# pixEmilyPdb.net
KiCad netlist of a schematic drawn in EAGLE
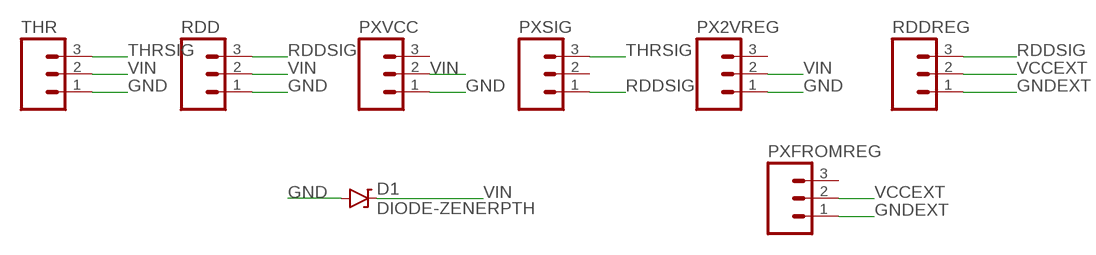
[diagram p0: schematic, sheet 1]

(export (version "E")
  (design (tool "Eeschema 10.0.6"))
  (components
    (comp (ref "D1")
      (value "DIODE-ZENERPTH")
      (footprint "eagle-import:DIODE-ZENER")
      (libsource (lib "eagle-import") (part "DIODE-ZENERPTH"))
    )
    (comp (ref "PX2VREG")
      (value "M03PTH")
      (footprint "eagle-import:1X03")
      (libsource (lib "eagle-import") (part "M03PTH"))
    )
    (comp (ref "PXFROMREG")
      (value "M03PTH")
      (footprint "eagle-import:1X03")
      (libsource (lib "eagle-import") (part "M03PTH"))
    )
    (comp (ref "PXSIG")
      (value "M03PTH")
      (footprint "eagle-import:1X03")
      (libsource (lib "eagle-import") (part "M03PTH"))
    )
    (comp (ref "PXVCC")
      (value "M03PTH")
      (footprint "eagle-import:1X03")
      (libsource (lib "eagle-import") (part "M03PTH"))
    )
    (comp (ref "RDD")
      (value "M03PTH")
      (footprint "eagle-import:1X03")
      (libsource (lib "eagle-import") (part "M03PTH"))
    )
    (comp (ref "RDDREG")
      (value "M03PTH")
      (footprint "eagle-import:1X03")
      (libsource (lib "eagle-import") (part "M03PTH"))
    )
    (comp (ref "THR")
      (value "M03PTH")
      (footprint "eagle-import:1X03")
      (libsource (lib "eagle-import") (part "M03PTH"))
    )
  )
  (nets
    (net (code "1") (name "/GND") (class "Default")
      (node (ref "D1") (pin "P$2") (pinfunction "A_P$2") (pintype "passive"))
      (node (ref "PX2VREG") (pin "1") (pinfunction "1_1") (pintype "passive"))
      (node (ref "PXVCC") (pin "1") (pinfunction "1_1") (pintype "passive"))
      (node (ref "RDD") (pin "1") (pinfunction "1_1") (pintype "passive"))
      (node (ref "THR") (pin "1") (pinfunction "1_1") (pintype "passive"))
    )
    (net (code "2") (name "/GNDEXT") (class "Default")
      (node (ref "PXFROMREG") (pin "1") (pinfunction "1_1") (pintype "passive"))
      (node (ref "RDDREG") (pin "1") (pinfunction "1_1") (pintype "passive"))
    )
    (net (code "3") (name "/RDDSIG") (class "Default")
      (node (ref "PXSIG") (pin "1") (pinfunction "1_1") (pintype "passive"))
      (node (ref "RDD") (pin "3") (pinfunction "3_3") (pintype "passive"))
      (node (ref "RDDREG") (pin "3") (pinfunction "3_3") (pintype "passive"))
    )
    (net (code "4") (name "/THRSIG") (class "Default")
      (node (ref "PXSIG") (pin "3") (pinfunction "3_3") (pintype "passive"))
      (node (ref "THR") (pin "3") (pinfunction "3_3") (pintype "passive"))
    )
    (net (code "5") (name "/VCCEXT") (class "Default")
      (node (ref "PXFROMREG") (pin "2") (pinfunction "2_2") (pintype "passive"))
      (node (ref "RDDREG") (pin "2") (pinfunction "2_2") (pintype "passive"))
    )
    (net (code "6") (name "/VIN") (class "Default")
      (node (ref "D1") (pin "P$1") (pinfunction "C_P$1") (pintype "passive"))
      (node (ref "PX2VREG") (pin "2") (pinfunction "2_2") (pintype "passive"))
      (node (ref "PXVCC") (pin "2") (pinfunction "2_2") (pintype "passive"))
      (node (ref "RDD") (pin "2") (pinfunction "2_2") (pintype "passive"))
      (node (ref "THR") (pin "2") (pinfunction "2_2") (pintype "passive"))
    )
    (net (code "7") (name "unconnected-(PX2VREG-Pad3)") (class "Default")
      (node (ref "PX2VREG") (pin "3") (pinfunction "3_3") (pintype "passive"))
    )
    (net (code "8") (name "unconnected-(PXFROMREG-Pad3)") (class "Default")
      (node (ref "PXFROMREG") (pin "3") (pinfunction "3_3") (pintype "passive"))
    )
    (net (code "9") (name "unconnected-(PXSIG-Pad2)") (class "Default")
      (node (ref "PXSIG") (pin "2") (pinfunction "2_2") (pintype "passive"))
    )
    (net (code "10") (name "unconnected-(PXVCC-Pad3)") (class "Default")
      (node (ref "PXVCC") (pin "3") (pinfunction "3_3") (pintype "passive"))
    )
  )
)
